# WirelessLampReceiver.net
KiCad netlist of a schematic drawn in Altium Designer
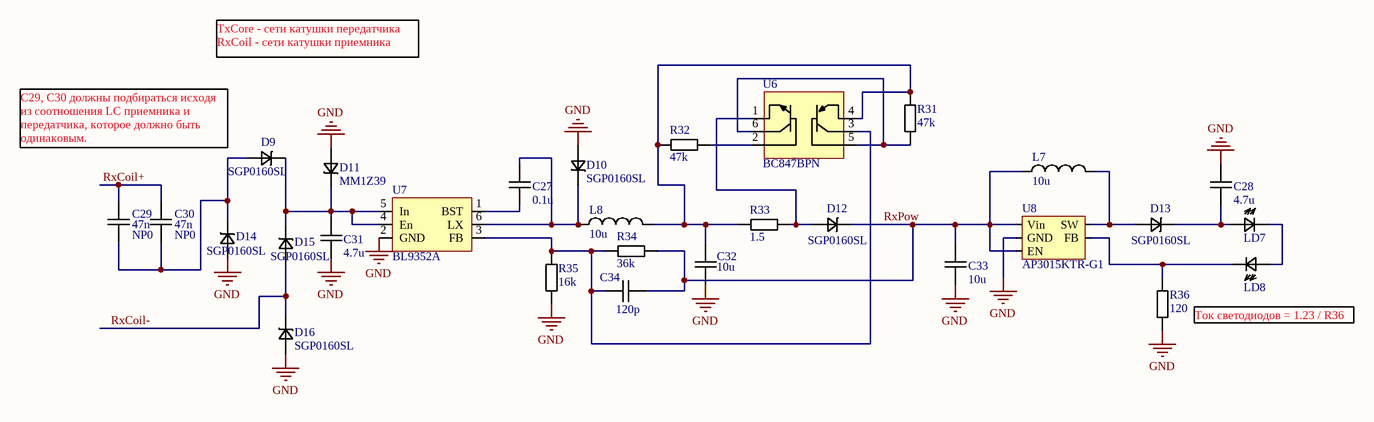
[diagram p0: WirelessLampReceiver.SchDoc]

(export (version "E")
  (design (tool "Eeschema 10.0.6"))
  (components
    (comp (ref "C27") (value "0.1u") (footprint "CAPC1608L") (libsource (lib "BMFT_lib") (part "Capacitor")))
    (comp (ref "C28") (value "4.7u") (footprint "CAPC2012L") (libsource (lib "BMFT_lib") (part "Capacitor")))
    (comp (ref "C29")
      (value "47n")
      (footprint "CAPC3216L")
      (fields
        (field (name "NAME") "NP0")
        (field (name "LCSC PART") "C21812")
        (field (name "PART") "GRM31M5C1H473JA01L")
        (field (name "VOLTAGE") "50V")
      )
      (libsource (lib "BMFT_lib") (part "Capacitor"))
    )
    (comp (ref "C30")
      (value "47n")
      (footprint "CAPC3216L")
      (fields
        (field (name "NAME") "NP0")
        (field (name "LCSC PART") "C21812")
        (field (name "PART") "GRM31M5C1H473JA01L")
        (field (name "VOLTAGE") "50V")
      )
      (libsource (lib "BMFT_lib") (part "Capacitor"))
    )
    (comp (ref "C31")
      (value "4.7u")
      (footprint "CAPC3216L")
      (fields (field (name "VOLTAGE") "50V"))
      (libsource (lib "BMFT_lib") (part "Capacitor"))
    )
    (comp (ref "C32") (value "10u") (footprint "CAPC3216L") (libsource (lib "BMFT_lib") (part "Capacitor")))
    (comp (ref "C33") (value "10u") (footprint "CAPC3216L") (libsource (lib "BMFT_lib") (part "Capacitor")))
    (comp (ref "C34") (value "120p") (footprint "CAPC1608L") (libsource (lib "BMFT_lib") (part "Capacitor")))
    (comp (ref "D9")
      (value "SGP0160SL")
      (footprint "SOD-323F")
      (fields (field (name "LCSC PART") "C110413"))
      (libsource (lib "BMFT_lib") (part "Schotky"))
    )
    (comp (ref "D10")
      (value "SGP0160SL")
      (footprint "SOD-323F")
      (fields (field (name "LCSC PART") "C110413"))
      (libsource (lib "BMFT_lib") (part "Schotky"))
    )
    (comp (ref "D11")
      (value "MM1Z39")
      (footprint "SOD123")
      (fields (field (name "LCSC PART") "C107460"))
      (libsource (lib "BMFT_lib") (part "Schotky"))
    )
    (comp (ref "D12")
      (value "SGP0160SL")
      (footprint "SOD-323F")
      (fields (field (name "LCSC PART") "C110413"))
      (libsource (lib "BMFT_lib") (part "Schotky"))
    )
    (comp (ref "D13")
      (value "SGP0160SL")
      (footprint "SOD-323F")
      (fields (field (name "LCSC PART") "C110413"))
      (libsource (lib "BMFT_lib") (part "Schotky"))
    )
    (comp (ref "D14")
      (value "SGP0160SL")
      (footprint "SOD-323F")
      (fields (field (name "LCSC PART") "C110413"))
      (libsource (lib "BMFT_lib") (part "Schotky"))
    )
    (comp (ref "D15")
      (value "SGP0160SL")
      (footprint "SOD-323F")
      (fields (field (name "LCSC PART") "C110413"))
      (libsource (lib "BMFT_lib") (part "Schotky"))
    )
    (comp (ref "D16")
      (value "SGP0160SL")
      (footprint "SOD-323F")
      (fields (field (name "LCSC PART") "C110413"))
      (libsource (lib "BMFT_lib") (part "Schotky"))
    )
    (comp (ref "L7")
      (value "10u")
      (footprint "Ind 3x3")
      (fields (field (name "PART") "PST031B-100MS") (field (name "LCSC PART") "C218837"))
      (libsource (lib "WirelessLamp_lib") (part "Inductor"))
    )
    (comp (ref "L8")
      (value "10u")
      (footprint "Ind 3x3")
      (fields (field (name "LCSC PART") "C218837") (field (name "PART") "PST031B-100MS"))
      (libsource (lib "WirelessLamp_lib") (part "Inductor"))
    )
    (comp (ref "LD7") (value "LED2825") (footprint "LED2835") (libsource (lib "BMFT_lib") (part "LED2825")))
    (comp (ref "LD8") (value "LED2825") (footprint "LED2835") (libsource (lib "BMFT_lib") (part "LED2825")))
    (comp (ref "R31") (value "47k") (footprint "RESC1608L") (libsource (lib "BMFT_lib") (part "Resistor")))
    (comp (ref "R32") (value "47k") (footprint "RESC1608L") (libsource (lib "BMFT_lib") (part "Resistor")))
    (comp (ref "R33") (value "1.5") (footprint "RESC3216L") (libsource (lib "BMFT_lib") (part "Resistor")))
    (comp (ref "R34") (value "36k") (footprint "RESC1608L") (libsource (lib "BMFT_lib") (part "Resistor")))
    (comp (ref "R35") (value "16k") (footprint "RESC1608L") (libsource (lib "BMFT_lib") (part "Resistor")))
    (comp (ref "R36") (value "120") (footprint "RESC2012L") (libsource (lib "BMFT_lib") (part "Resistor")))
    (comp (ref "U6")
      (value "BC847BPN")
      (footprint "sot-363-6")
      (fields (field (name "LCSC PART") "C8655") (field (name "PART") "BC847BPN,115"))
      (libsource (lib "WirelessLamp_lib") (part "BC847BPN"))
    )
    (comp (ref "U7")
      (value "BL9352A")
      (footprint "SOT26A-6N")
      (description "StepDown Regulator")
      (fields (field (name "LCSC PART") "C193985"))
      (libsource (lib "WirelessLamp_lib") (part "BL9352A"))
    )
    (comp (ref "U8")
      (value "AP3015KTR-G1")
      (footprint "SOT23-5AL")
      (fields (field (name "LCSC PART") "C151334"))
      (libsource (lib "BMFT_lib") (part "TPS6104x"))
    )
  )
  (nets
    (net (code "1") (name "/RxCoil+") (class "Default")
      (node (ref "C29") (pin "2") (pintype "passive"))
      (node (ref "C30") (pin "1") (pintype "passive"))
    )
    (net (code "2") (name "/RxCoil-") (class "Default")
      (node (ref "D15") (pin "1") (pintype "passive"))
      (node (ref "D16") (pin "2") (pintype "passive"))
    )
    (net (code "3") (name "/RxPow") (class "Default")
      (node (ref "C33") (pin "2") (pintype "passive"))
      (node (ref "C34") (pin "2") (pintype "passive"))
      (node (ref "D12") (pin "2") (pintype "passive"))
      (node (ref "L7") (pin "1") (pintype "passive"))
      (node (ref "R34") (pin "2") (pintype "passive"))
      (node (ref "U8") (pin "4") (pinfunction "EN_4") (pintype "passive"))
      (node (ref "U8") (pin "5") (pinfunction "Vin_5") (pintype "power_in"))
    )
    (net (code "4") (name "GND") (class "Default")
      (node (ref "C28") (pin "2") (pintype "passive"))
      (node (ref "C31") (pin "1") (pintype "passive"))
      (node (ref "C32") (pin "1") (pintype "passive"))
      (node (ref "C33") (pin "1") (pintype "passive"))
      (node (ref "D10") (pin "1") (pintype "passive"))
      (node (ref "D11") (pin "1") (pintype "passive"))
      (node (ref "D14") (pin "1") (pintype "passive"))
      (node (ref "D16") (pin "1") (pintype "passive"))
      (node (ref "R35") (pin "1") (pintype "passive"))
      (node (ref "R36") (pin "1") (pintype "passive"))
      (node (ref "U7") (pin "2") (pinfunction "GND_2") (pintype "power_in"))
      (node (ref "U8") (pin "2") (pinfunction "GND_2") (pintype "power_in"))
    )
    (net (code "5") (name "Net-(C28-Pad1)") (class "Default")
      (node (ref "C28") (pin "1") (pintype "passive"))
      (node (ref "D13") (pin "2") (pintype "passive"))
      (node (ref "LD7") (pin "2") (pintype "passive"))
    )
    (net (code "6") (name "Net-(C29-Pad1)") (class "Default")
      (node (ref "C29") (pin "1") (pintype "passive"))
      (node (ref "C30") (pin "2") (pintype "passive"))
      (node (ref "D14") (pin "2") (pintype "passive"))
      (node (ref "D9") (pin "1") (pintype "passive"))
    )
    (net (code "7") (name "Net-(LD7-Pad1)") (class "Default")
      (node (ref "LD7") (pin "1") (pintype "passive"))
      (node (ref "LD8") (pin "2") (pintype "passive"))
    )
    (net (code "8") (name "Net-(U6-bn1)") (class "Default")
      (node (ref "R32") (pin "2") (pintype "passive"))
      (node (ref "U6") (pin "2") (pinfunction "bn1_2") (pintype "passive"))
    )
    (net (code "9") (name "Net-(U6-bp2)") (class "Default")
      (node (ref "R31") (pin "1") (pintype "passive"))
      (node (ref "U6") (pin "5") (pinfunction "bp2_5") (pintype "passive"))
      (node (ref "U6") (pin "6") (pinfunction "cn1_6") (pintype "passive"))
    )
    (net (code "10") (name "Net-(U6-cp2)") (class "Default")
      (node (ref "C34") (pin "1") (pintype "passive"))
      (node (ref "R34") (pin "1") (pintype "passive"))
      (node (ref "R35") (pin "2") (pintype "passive"))
      (node (ref "U6") (pin "3") (pinfunction "cp2_3") (pintype "passive"))
      (node (ref "U7") (pin "3") (pinfunction "FB_3") (pintype "passive"))
    )
    (net (code "11") (name "Net-(U6-en1)") (class "Default")
      (node (ref "D12") (pin "1") (pintype "passive"))
      (node (ref "R33") (pin "2") (pintype "passive"))
      (node (ref "U6") (pin "1") (pinfunction "en1_1") (pintype "passive"))
    )
    (net (code "12") (name "Net-(U6-ep2)") (class "Default")
      (node (ref "C32") (pin "2") (pintype "passive"))
      (node (ref "L8") (pin "2") (pintype "passive"))
      (node (ref "R31") (pin "2") (pintype "passive"))
      (node (ref "R32") (pin "1") (pintype "passive"))
      (node (ref "R33") (pin "1") (pintype "passive"))
      (node (ref "U6") (pin "4") (pinfunction "ep2_4") (pintype "passive"))
    )
    (net (code "13") (name "Net-(U7-BST)") (class "Default")
      (node (ref "C27") (pin "1") (pintype "passive"))
      (node (ref "U7") (pin "1") (pinfunction "BST_1") (pintype "passive"))
    )
    (net (code "14") (name "Net-(U7-En)") (class "Default")
      (node (ref "C31") (pin "2") (pintype "passive"))
      (node (ref "D11") (pin "2") (pintype "passive"))
      (node (ref "D15") (pin "2") (pintype "passive"))
      (node (ref "D9") (pin "2") (pintype "passive"))
      (node (ref "U7") (pin "4") (pinfunction "En_4") (pintype "passive"))
      (node (ref "U7") (pin "5") (pinfunction "In_5") (pintype "power_in"))
    )
    (net (code "15") (name "Net-(U7-LX)") (class "Default")
      (node (ref "C27") (pin "2") (pintype "passive"))
      (node (ref "D10") (pin "2") (pintype "passive"))
      (node (ref "L8") (pin "1") (pintype "passive"))
      (node (ref "U7") (pin "6") (pinfunction "LX_6") (pintype "passive"))
    )
    (net (code "16") (name "Net-(U8-FB)") (class "Default")
      (node (ref "LD8") (pin "1") (pintype "passive"))
      (node (ref "R36") (pin "2") (pintype "passive"))
      (node (ref "U8") (pin "3") (pinfunction "FB_3") (pintype "passive"))
    )
    (net (code "17") (name "Net-(U8-SW)") (class "Default")
      (node (ref "D13") (pin "1") (pintype "passive"))
      (node (ref "L7") (pin "2") (pintype "passive"))
      (node (ref "U8") (pin "1") (pinfunction "SW_1") (pintype "power_in"))
    )
  )
)
